# TSOC_ESP32S.net
KiCad netlist of a schematic drawn in EAGLE
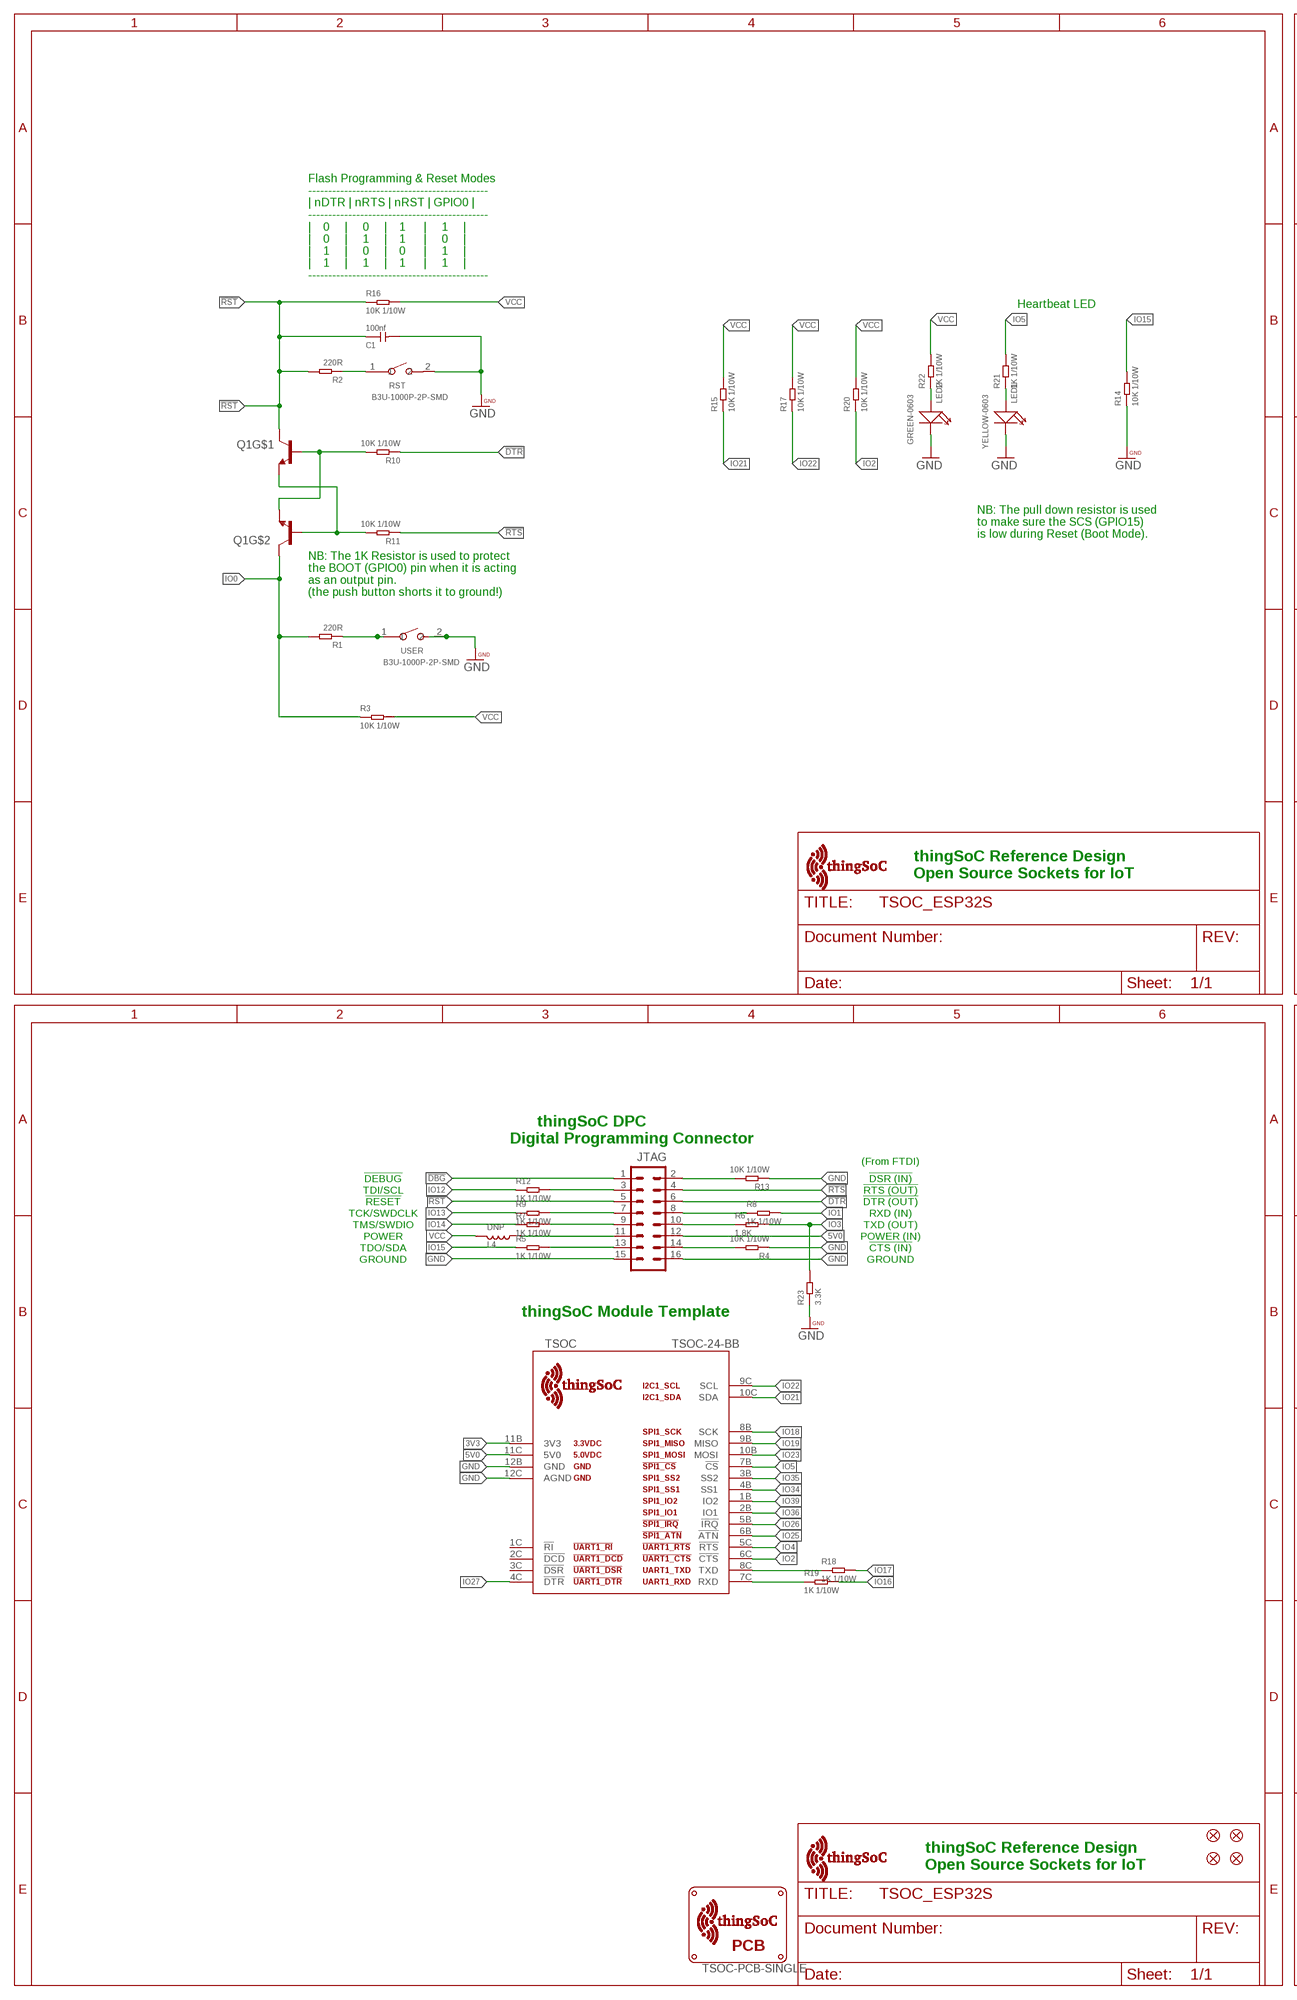
[diagram p0: schematic, sheet 1, part 1 of 2]
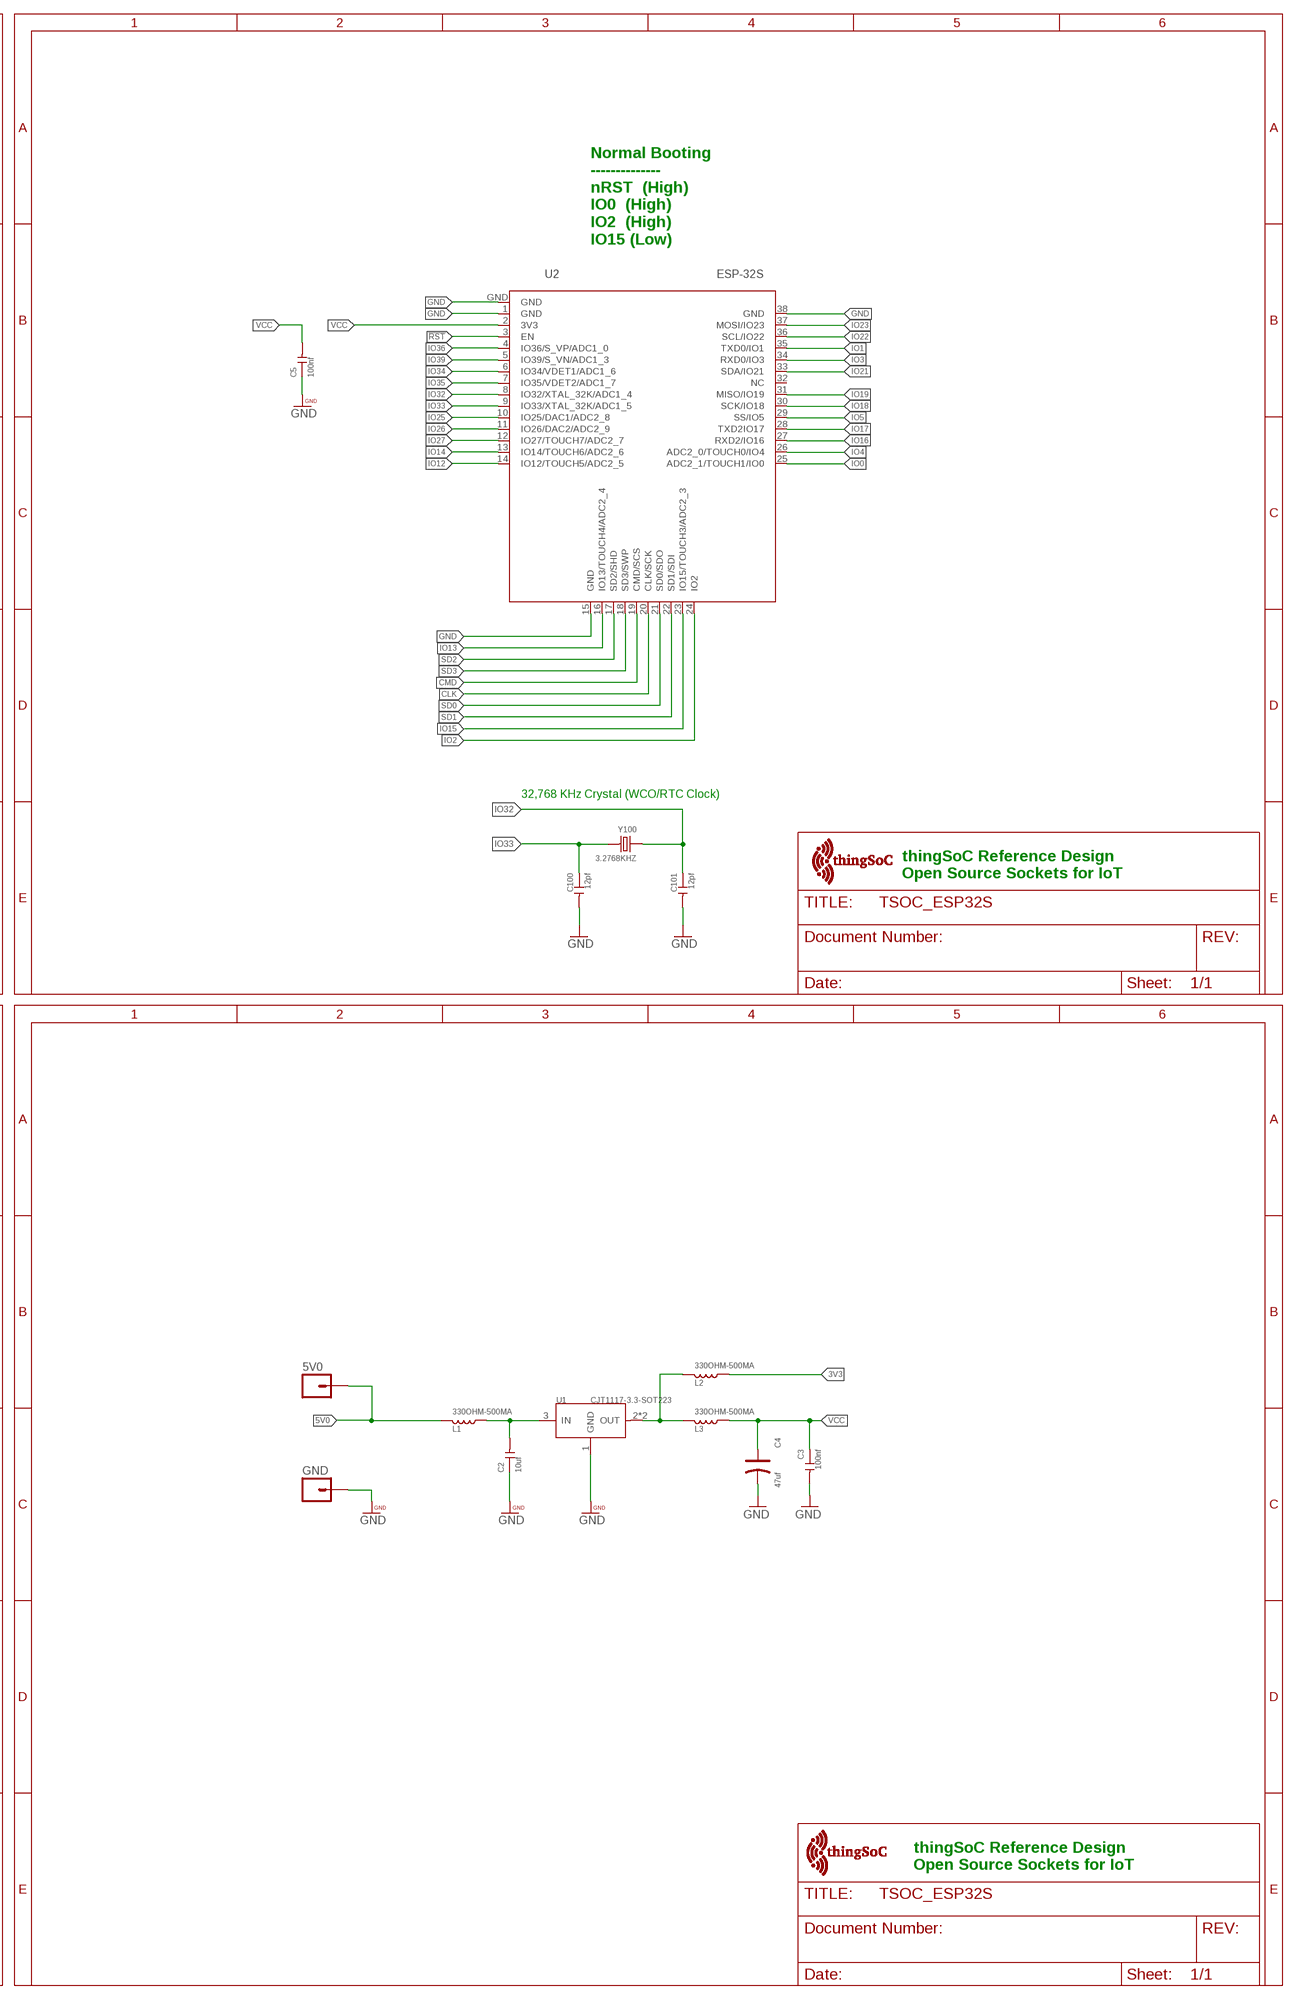
[diagram p1: schematic, sheet 1, part 2 of 2]

(export (version "E")
  (design (tool "Eeschema 10.0.6"))
  (components
    (comp (ref "$$U$1")
      (value "TSOC-LOGO-SMALL")
      (footprint "eagle-import:TSOC-LOGO-SML")
      (libsource (lib "eagle-import") (part "TSOC-LOGO-SMALL"))
    )
    (comp (ref "$$U$2")
      (value "TSOC-LOGO-SMALL")
      (footprint "eagle-import:TSOC-LOGO-SML")
      (libsource (lib "eagle-import") (part "TSOC-LOGO-SMALL"))
    )
    (comp (ref "5V0")
      (value "M01PTH")
      (footprint "eagle-import:1X01")
      (libsource (lib "eagle-import") (part "M01PTH"))
    )
    (comp (ref "BRD")
      (value "TSOC-PCB-SINGLE")
      (footprint "eagle-import:TSOC-BB-BRD-DIM")
      (libsource (lib "eagle-import") (part "TSOC-PCB-SINGLE"))
    )
    (comp (ref "C1")
      (value "100nf")
      (footprint "eagle-import:C0603")
      (fields (field (name "MPN") "CC0603KRX7R9BB104"))
      (libsource (lib "eagle-import") (part "CERAMIC-100NF-50V-10%-X7R(0603)"))
    )
    (comp (ref "C2")
      (value "10uf")
      (footprint "eagle-import:C0603")
      (fields (field (name "MPN") "CC0603KRX5R6BB106"))
      (libsource (lib "eagle-import") (part "CERAMIC-10UF-10V-10%-X5R(0603)"))
    )
    (comp (ref "C3")
      (value "100nf")
      (footprint "eagle-import:C0603")
      (fields (field (name "MPN") "CC0603KRX7R9BB104"))
      (libsource (lib "eagle-import") (part "CERAMIC-100NF-50V-10%-X7R(0603)"))
    )
    (comp (ref "C4")
      (value "47uf")
      (footprint "eagle-import:AVX-A")
      (fields (field (name "MPN") "TAJA476*006#NJ"))
      (libsource (lib "eagle-import") (part "TANTALUM-SMD-47UF-6.3V(AVX-A)"))
    )
    (comp (ref "C5")
      (value "100nf")
      (footprint "eagle-import:C0603")
      (fields (field (name "MPN") "CC0603KRX5R6BB106"))
      (libsource (lib "eagle-import") (part "CERAMIC-10UF-10V-10%-X5R(0603)"))
    )
    (comp (ref "C100")
      (value "12pf")
      (footprint "eagle-import:C0603")
      (fields (field (name "MPN") "CC0603JRNPO9BN120"))
      (libsource (lib "eagle-import") (part "CERAMIC-12PF-50V-5%-NPO(0603)"))
    )
    (comp (ref "C101")
      (value "12pf")
      (footprint "eagle-import:C0603")
      (fields (field (name "MPN") "CC0603JRNPO9BN120"))
      (libsource (lib "eagle-import") (part "CERAMIC-12PF-50V-5%-NPO(0603)"))
    )
    (comp (ref "FID1")
      (value "FIDUCIALUFIDUCIAL")
      (footprint "eagle-import:MICRO-FIDUCIAL")
      (libsource (lib "eagle-import") (part "FIDUCIALUFIDUCIAL"))
    )
    (comp (ref "FID2")
      (value "FIDUCIALUFIDUCIAL")
      (footprint "eagle-import:MICRO-FIDUCIAL")
      (libsource (lib "eagle-import") (part "FIDUCIALUFIDUCIAL"))
    )
    (comp (ref "FID3")
      (value "FIDUCIALUFIDUCIAL")
      (footprint "eagle-import:MICRO-FIDUCIAL")
      (libsource (lib "eagle-import") (part "FIDUCIALUFIDUCIAL"))
    )
    (comp (ref "FID4")
      (value "FIDUCIALUFIDUCIAL")
      (footprint "eagle-import:MICRO-FIDUCIAL")
      (libsource (lib "eagle-import") (part "FIDUCIALUFIDUCIAL"))
    )
    (comp (ref "GND")
      (value "M01PTH")
      (footprint "eagle-import:1X01")
      (libsource (lib "eagle-import") (part "M01PTH"))
    )
    (comp (ref "JTAG")
      (value "M08X2")
      (footprint "eagle-import:2X8")
      (libsource (lib "eagle-import") (part "M08X2"))
    )
    (comp (ref "L1")
      (value "330OHM-500MA")
      (footprint "eagle-import:L0603")
      (fields (field (name "MPN") "BLM18AG121SN1D"))
      (libsource (lib "eagle-import") (part "SMD-FERRITE-CHIP-120-OHM-500MA(0603)"))
    )
    (comp (ref "L2")
      (value "330OHM-500MA")
      (footprint "eagle-import:L0603")
      (fields (field (name "MPN") "BLM18AG121SN1D"))
      (libsource (lib "eagle-import") (part "SMD-FERRITE-CHIP-120-OHM-500MA(0603)"))
    )
    (comp (ref "L3")
      (value "330OHM-500MA")
      (footprint "eagle-import:L0603")
      (fields (field (name "MPN") "BLM18AG121SN1D"))
      (libsource (lib "eagle-import") (part "SMD-FERRITE-CHIP-120-OHM-500MA(0603)"))
    )
    (comp (ref "L4")
      (value "DNP")
      (footprint "eagle-import:L0603")
      (fields (field (name "MPN") "BLM18AG121SN1D"))
      (libsource (lib "eagle-import") (part "SMD-FERRITE-CHIP-120-OHM-500MA(0603)"))
    )
    (comp (ref "LED1")
      (value "YELLOW-0603")
      (footprint "eagle-import:LED-0603")
      (fields (field (name "MPN") "19-217-Y5C-AM1N1VY-3T"))
      (libsource (lib "eagle-import") (part "SMD-LED-CLEAR-YELLOW(0603)"))
    )
    (comp (ref "LED2")
      (value "GREEN-0603")
      (footprint "eagle-import:LED-0603")
      (fields (field (name "MPN") "19-217-G7C-AN1P2-3T"))
      (libsource (lib "eagle-import") (part "SMD-LED-CLEAR-GREEN(0603)"))
    )
    (comp (ref "Q1")
      (value "MMBT2222A")
      (footprint "eagle-import:SOT363")
      (libsource (lib "eagle-import") (part "MMDT3904"))
    )
    (comp (ref "R1")
      (value "220R")
      (footprint "eagle-import:R0603")
      (fields (field (name "MPN") "RC0603JR-07220RL"))
      (libsource (lib "eagle-import") (part "SMD-RES-220R-5%-1/10W(0603)"))
    )
    (comp (ref "R2")
      (value "220R")
      (footprint "eagle-import:R0603")
      (fields (field (name "MPN") "RC0603JR-07220RL"))
      (libsource (lib "eagle-import") (part "SMD-RES-220R-5%-1/10W(0603)"))
    )
    (comp (ref "R3")
      (value "10K 1/10W")
      (footprint "eagle-import:R0603")
      (fields (field (name "MPN") "RC0603JR-0710KL"))
      (libsource (lib "eagle-import") (part "SMD-RES-10K-5%-1/10W(0603)"))
    )
    (comp (ref "R4")
      (value "10K 1/10W")
      (footprint "eagle-import:R0603")
      (fields (field (name "MPN") "RC0603JR-0710KL"))
      (libsource (lib "eagle-import") (part "SMD-RES-10K-5%-1/10W(0603)"))
    )
    (comp (ref "R5")
      (value "1K 1/10W")
      (footprint "eagle-import:R0603")
      (fields (field (name "MPN") "RC0603JR-071KL"))
      (libsource (lib "eagle-import") (part "SMD-RES-1K-5%-1/10W(0603)"))
    )
    (comp (ref "R6")
      (value "1.8K")
      (footprint "eagle-import:R0603")
      (fields (field (name "MPN") "RC0603FR-071K8L"))
      (libsource (lib "eagle-import") (part "SMD-RES-1.8K-1%-1/10W(0603)"))
    )
    (comp (ref "R7")
      (value "1K 1/10W")
      (footprint "eagle-import:R0603")
      (fields (field (name "MPN") "RC0603JR-071KL"))
      (libsource (lib "eagle-import") (part "SMD-RES-1K-5%-1/10W(0603)"))
    )
    (comp (ref "R8")
      (value "1K 1/10W")
      (footprint "eagle-import:R0603")
      (fields (field (name "MPN") "RC0603JR-071KL"))
      (libsource (lib "eagle-import") (part "SMD-RES-1K-5%-1/10W(0603)"))
    )
    (comp (ref "R9")
      (value "1K 1/10W")
      (footprint "eagle-import:R0603")
      (fields (field (name "MPN") "RC0603JR-071KL"))
      (libsource (lib "eagle-import") (part "SMD-RES-1K-5%-1/10W(0603)"))
    )
    (comp (ref "R10")
      (value "10K 1/10W")
      (footprint "eagle-import:R0603")
      (fields (field (name "MPN") "RC0603JR-0710KL"))
      (libsource (lib "eagle-import") (part "SMD-RES-10K-5%-1/10W(0603)"))
    )
    (comp (ref "R11")
      (value "10K 1/10W")
      (footprint "eagle-import:R0603")
      (fields (field (name "MPN") "RC0603JR-0710KL"))
      (libsource (lib "eagle-import") (part "SMD-RES-10K-5%-1/10W(0603)"))
    )
    (comp (ref "R12")
      (value "1K 1/10W")
      (footprint "eagle-import:R0603")
      (fields (field (name "MPN") "RC0603JR-071KL"))
      (libsource (lib "eagle-import") (part "SMD-RES-1K-5%-1/10W(0603)"))
    )
    (comp (ref "R13")
      (value "10K 1/10W")
      (footprint "eagle-import:R0603")
      (fields (field (name "MPN") "RC0603JR-0710KL"))
      (libsource (lib "eagle-import") (part "SMD-RES-10K-5%-1/10W(0603)"))
    )
    (comp (ref "R14")
      (value "10K 1/10W")
      (footprint "eagle-import:R0603")
      (fields (field (name "MPN") "RC0603JR-0710KL"))
      (libsource (lib "eagle-import") (part "SMD-RES-10K-5%-1/10W(0603)"))
    )
    (comp (ref "R15")
      (value "10K 1/10W")
      (footprint "eagle-import:R0603")
      (fields (field (name "MPN") "RC0603JR-0710KL"))
      (libsource (lib "eagle-import") (part "SMD-RES-10K-5%-1/10W(0603)"))
    )
    (comp (ref "R16")
      (value "10K 1/10W")
      (footprint "eagle-import:R0603")
      (fields (field (name "MPN") "RC0603JR-0710KL"))
      (libsource (lib "eagle-import") (part "SMD-RES-10K-5%-1/10W(0603)"))
    )
    (comp (ref "R17")
      (value "10K 1/10W")
      (footprint "eagle-import:R0603")
      (fields (field (name "MPN") "RC0603JR-0710KL"))
      (libsource (lib "eagle-import") (part "SMD-RES-10K-5%-1/10W(0603)"))
    )
    (comp (ref "R18")
      (value "1K 1/10W")
      (footprint "eagle-import:R0603")
      (fields (field (name "MPN") "RC0603JR-071KL"))
      (libsource (lib "eagle-import") (part "SMD-RES-1K-5%-1/10W(0603)"))
    )
    (comp (ref "R19")
      (value "1K 1/10W")
      (footprint "eagle-import:R0603")
      (fields (field (name "MPN") "RC0603JR-071KL"))
      (libsource (lib "eagle-import") (part "SMD-RES-1K-5%-1/10W(0603)"))
    )
    (comp (ref "R20")
      (value "10K 1/10W")
      (footprint "eagle-import:R0603")
      (fields (field (name "MPN") "RC0603JR-0710KL"))
      (libsource (lib "eagle-import") (part "SMD-RES-10K-5%-1/10W(0603)"))
    )
    (comp (ref "R21")
      (value "1K 1/10W")
      (footprint "eagle-import:R0603")
      (fields (field (name "MPN") "RC0603JR-071KL"))
      (libsource (lib "eagle-import") (part "SMD-RES-1K-5%-1/10W(0603)"))
    )
    (comp (ref "R22")
      (value "1K 1/10W")
      (footprint "eagle-import:R0603")
      (fields (field (name "MPN") "RC0603JR-071KL"))
      (libsource (lib "eagle-import") (part "SMD-RES-1K-5%-1/10W(0603)"))
    )
    (comp (ref "R23")
      (value "3.3K")
      (footprint "eagle-import:R0603")
      (fields (field (name "MPN") "RC0603FR-073K3L"))
      (libsource (lib "eagle-import") (part "SMD-RES-3.3K-1%-1/10W(0603)"))
    )
    (comp (ref "RST")
      (value "B3U-1000P-2P-SMD")
      (footprint "eagle-import:SW2-2.6-3.0X2.5X1.2+0.4MM")
      (libsource (lib "eagle-import") (part "SMD-BUTTON(2P-3.0X2.5X1.2+0.4MM)-B3U-1000P-2P-SMD"))
    )
    (comp (ref "TSOC")
      (value "TSOC-24-BB")
      (footprint "eagle-import:TSOC-BB-S24")
      (libsource (lib "eagle-import") (part "TSOC-24-BB"))
    )
    (comp (ref "U$101")
      (value "TSOC-LOGO-SMALL")
      (footprint "eagle-import:TSOC-LOGO-SML")
      (libsource (lib "eagle-import") (part "TSOC-LOGO-SMALL"))
    )
    (comp (ref "U$102")
      (value "TSOC-LOGO-LRG")
      (footprint "eagle-import:TSOC-LOGO-LRG")
      (libsource (lib "eagle-import") (part "TSOC-LOGO-LRG"))
    )
    (comp (ref "U1")
      (value "CJT1117-3.3-SOT223")
      (footprint "eagle-import:SOT-223")
      (fields (field (name "MPN") "CJT1117-3.3"))
      (libsource (lib "eagle-import") (part "PMIC-CJT1117-3.3(SOT223)"))
    )
    (comp (ref "U2")
      (value "ESP-32S")
      (footprint "eagle-import:ESP-32S")
      (libsource (lib "eagle-import") (part "ESP-32S"))
    )
    (comp (ref "USER")
      (value "B3U-1000P-2P-SMD")
      (footprint "eagle-import:SW2-2.6-3.0X2.5X1.2+0.4MM")
      (libsource (lib "eagle-import") (part "SMD-BUTTON(2P-3.0X2.5X1.2+0.4MM)-B3U-1000P-2P-SMD"))
    )
    (comp (ref "Y100")
      (value "3.2768KHZ")
      (footprint "eagle-import:X2-SMD-L2.0X1.2X0.55MM")
      (fields (field (name "MPN") "FC-12M"))
      (libsource (lib "eagle-import") (part "SMD-CRYSTAL-32.768KHZ-12.5PF-20PPM-90K(2P-L2.0X1.2MM)"))
    )
  )
  (nets
    (net (code "1") (name "/~{DBG}") (class "Default")
      (node (ref "JTAG") (pin "1") (pinfunction "1_1") (pintype "passive"))
    )
    (net (code "2") (name "/~{DTR}") (class "Default")
      (node (ref "JTAG") (pin "6") (pinfunction "6_6") (pintype "passive"))
      (node (ref "R10") (pin "1") (pinfunction "1_1") (pintype "passive"))
    )
    (net (code "3") (name "/~{RST}") (class "Default")
      (node (ref "C1") (pin "1") (pinfunction "1_1") (pintype "passive"))
      (node (ref "JTAG") (pin "5") (pinfunction "5_5") (pintype "passive"))
      (node (ref "Q1") (pin "3") (pinfunction "C_3") (pintype "passive"))
      (node (ref "R16") (pin "1") (pinfunction "1_1") (pintype "passive"))
      (node (ref "R2") (pin "2") (pinfunction "2_2") (pintype "passive"))
      (node (ref "U2") (pin "3") (pinfunction "EN_3") (pintype "bidirectional"))
    )
    (net (code "4") (name "/~{RTS}") (class "Default")
      (node (ref "JTAG") (pin "4") (pinfunction "4_4") (pintype "passive"))
      (node (ref "R11") (pin "1") (pinfunction "1_1") (pintype "passive"))
    )
    (net (code "5") (name "3V3") (class "Default")
      (node (ref "L2") (pin "2") (pinfunction "2_2") (pintype "passive"))
      (node (ref "TSOC") (pin "11B") (pinfunction "3V3_11B") (pintype "bidirectional"))
    )
    (net (code "6") (name "5V0") (class "Default")
      (node (ref "5V0") (pin "1") (pinfunction "1_1") (pintype "passive"))
      (node (ref "JTAG") (pin "12") (pinfunction "12_12") (pintype "passive"))
      (node (ref "L1") (pin "1") (pinfunction "1_1") (pintype "passive"))
      (node (ref "TSOC") (pin "11C") (pinfunction "5V0_11C") (pintype "bidirectional"))
    )
    (net (code "7") (name "CLK") (class "Default")
      (node (ref "U2") (pin "20") (pinfunction "CLK/SCK_20") (pintype "bidirectional"))
    )
    (net (code "8") (name "CMD") (class "Default")
      (node (ref "U2") (pin "19") (pinfunction "CMD/SCS_19") (pintype "bidirectional"))
    )
    (net (code "9") (name "GND") (class "Default")
      (node (ref "C1") (pin "2") (pinfunction "2_2") (pintype "passive"))
      (node (ref "C100") (pin "2") (pinfunction "2_2") (pintype "passive"))
      (node (ref "C101") (pin "2") (pinfunction "2_2") (pintype "passive"))
      (node (ref "C2") (pin "1") (pinfunction "1_1") (pintype "passive"))
      (node (ref "C3") (pin "2") (pinfunction "2_2") (pintype "passive"))
      (node (ref "C4") (pin "-") (pinfunction "-_-") (pintype "passive"))
      (node (ref "C5") (pin "1") (pinfunction "1_1") (pintype "passive"))
      (node (ref "GND") (pin "1") (pinfunction "1_1") (pintype "passive"))
      (node (ref "JTAG") (pin "15") (pinfunction "15_15") (pintype "passive"))
      (node (ref "JTAG") (pin "16") (pinfunction "16_16") (pintype "passive"))
      (node (ref "LED1") (pin "-") (pinfunction "-_-") (pintype "passive"))
      (node (ref "LED2") (pin "-") (pinfunction "-_-") (pintype "passive"))
      (node (ref "R13") (pin "1") (pinfunction "1_1") (pintype "passive"))
      (node (ref "R14") (pin "1") (pinfunction "1_1") (pintype "passive"))
      (node (ref "R23") (pin "1") (pinfunction "1_1") (pintype "passive"))
      (node (ref "R4") (pin "1") (pinfunction "1_1") (pintype "passive"))
      (node (ref "RST") (pin "2") (pinfunction "2_2") (pintype "bidirectional"))
      (node (ref "TSOC") (pin "12B") (pinfunction "GND_12B") (pintype "bidirectional"))
      (node (ref "TSOC") (pin "12C") (pinfunction "AGND_12C") (pintype "bidirectional"))
      (node (ref "U1") (pin "1") (pinfunction "GND_1") (pintype "bidirectional"))
      (node (ref "U2") (pin "1") (pinfunction "GND_1") (pintype "bidirectional"))
      (node (ref "U2") (pin "15") (pinfunction "GND_15") (pintype "bidirectional"))
      (node (ref "U2") (pin "38") (pinfunction "GND_38") (pintype "bidirectional"))
      (node (ref "U2") (pin "GND") (pinfunction "GND_GND") (pintype "bidirectional"))
      (node (ref "USER") (pin "2") (pinfunction "2_2") (pintype "bidirectional"))
    )
    (net (code "10") (name "IO0") (class "Default")
      (node (ref "Q1") (pin "6") (pinfunction "C_6") (pintype "passive"))
      (node (ref "R1") (pin "2") (pinfunction "2_2") (pintype "passive"))
      (node (ref "R3") (pin "1") (pinfunction "1_1") (pintype "passive"))
      (node (ref "U2") (pin "25") (pinfunction "ADC2_1/TOUCH1/IO0_25") (pintype "bidirectional"))
    )
    (net (code "11") (name "IO1") (class "Default")
      (node (ref "R8") (pin "2") (pinfunction "2_2") (pintype "passive"))
      (node (ref "U2") (pin "35") (pinfunction "TXD0/IO1_35") (pintype "bidirectional"))
    )
    (net (code "12") (name "IO2") (class "Default")
      (node (ref "R20") (pin "1") (pinfunction "1_1") (pintype "passive"))
      (node (ref "TSOC") (pin "6C") (pinfunction "~{CTS}_6C") (pintype "bidirectional"))
      (node (ref "U2") (pin "24") (pinfunction "IO2_24") (pintype "bidirectional"))
    )
    (net (code "13") (name "IO3") (class "Default")
      (node (ref "R23") (pin "2") (pinfunction "2_2") (pintype "passive"))
      (node (ref "R6") (pin "2") (pinfunction "2_2") (pintype "passive"))
      (node (ref "U2") (pin "34") (pinfunction "RXD0/IO3_34") (pintype "bidirectional"))
    )
    (net (code "14") (name "IO4") (class "Default")
      (node (ref "TSOC") (pin "5C") (pinfunction "~{RTS}_5C") (pintype "bidirectional"))
      (node (ref "U2") (pin "26") (pinfunction "ADC2_0/TOUCH0/IO4_26") (pintype "bidirectional"))
    )
    (net (code "15") (name "IO5") (class "Default")
      (node (ref "R21") (pin "2") (pinfunction "2_2") (pintype "passive"))
      (node (ref "TSOC") (pin "7B") (pinfunction "~{CS}_7B") (pintype "bidirectional"))
      (node (ref "U2") (pin "29") (pinfunction "SS/IO5_29") (pintype "bidirectional"))
    )
    (net (code "16") (name "IO12") (class "Default")
      (node (ref "R12") (pin "1") (pinfunction "1_1") (pintype "passive"))
      (node (ref "U2") (pin "14") (pinfunction "IO12/TOUCH5/ADC2_5_14") (pintype "bidirectional"))
    )
    (net (code "17") (name "IO13") (class "Default")
      (node (ref "R9") (pin "1") (pinfunction "1_1") (pintype "passive"))
      (node (ref "U2") (pin "16") (pinfunction "IO13/TOUCH4/ADC2_4_16") (pintype "bidirectional"))
    )
    (net (code "18") (name "IO14") (class "Default")
      (node (ref "R7") (pin "1") (pinfunction "1_1") (pintype "passive"))
      (node (ref "U2") (pin "13") (pinfunction "IO14/TOUCH6/ADC2_6_13") (pintype "bidirectional"))
    )
    (net (code "19") (name "IO15") (class "Default")
      (node (ref "R14") (pin "2") (pinfunction "2_2") (pintype "passive"))
      (node (ref "R5") (pin "1") (pinfunction "1_1") (pintype "passive"))
      (node (ref "U2") (pin "23") (pinfunction "IO15/TOUCH3/ADC2_3_23") (pintype "bidirectional"))
    )
    (net (code "20") (name "IO16") (class "Default")
      (node (ref "R19") (pin "2") (pinfunction "2_2") (pintype "passive"))
      (node (ref "U2") (pin "27") (pinfunction "RXD2/IO16_27") (pintype "bidirectional"))
    )
    (net (code "21") (name "IO17") (class "Default")
      (node (ref "R18") (pin "2") (pinfunction "2_2") (pintype "passive"))
      (node (ref "U2") (pin "28") (pinfunction "TXD2IO17_28") (pintype "bidirectional"))
    )
    (net (code "22") (name "IO18") (class "Default")
      (node (ref "TSOC") (pin "8B") (pinfunction "SCK_8B") (pintype "bidirectional"))
      (node (ref "U2") (pin "30") (pinfunction "SCK/IO18_30") (pintype "bidirectional"))
    )
    (net (code "23") (name "IO19") (class "Default")
      (node (ref "TSOC") (pin "9B") (pinfunction "MISO_9B") (pintype "bidirectional"))
      (node (ref "U2") (pin "31") (pinfunction "MISO/IO19_31") (pintype "bidirectional"))
    )
    (net (code "24") (name "IO21") (class "Default")
      (node (ref "R15") (pin "1") (pinfunction "1_1") (pintype "passive"))
      (node (ref "TSOC") (pin "10C") (pinfunction "SDA_10C") (pintype "bidirectional"))
      (node (ref "U2") (pin "33") (pinfunction "SDA/IO21_33") (pintype "bidirectional"))
    )
    (net (code "25") (name "IO22") (class "Default")
      (node (ref "R17") (pin "1") (pinfunction "1_1") (pintype "passive"))
      (node (ref "TSOC") (pin "9C") (pinfunction "SCL_9C") (pintype "bidirectional"))
      (node (ref "U2") (pin "36") (pinfunction "SCL/IO22_36") (pintype "bidirectional"))
    )
    (net (code "26") (name "IO23") (class "Default")
      (node (ref "TSOC") (pin "10B") (pinfunction "MOSI_10B") (pintype "bidirectional"))
      (node (ref "U2") (pin "37") (pinfunction "MOSI/IO23_37") (pintype "bidirectional"))
    )
    (net (code "27") (name "IO25") (class "Default")
      (node (ref "TSOC") (pin "6B") (pinfunction "~{ATN}_6B") (pintype "bidirectional"))
      (node (ref "U2") (pin "10") (pinfunction "IO25/DAC1/ADC2_8_10") (pintype "bidirectional"))
    )
    (net (code "28") (name "IO26") (class "Default")
      (node (ref "TSOC") (pin "5B") (pinfunction "~{IRQ}_5B") (pintype "bidirectional"))
      (node (ref "U2") (pin "11") (pinfunction "IO26/DAC2/ADC2_9_11") (pintype "bidirectional"))
    )
    (net (code "29") (name "IO27") (class "Default")
      (node (ref "TSOC") (pin "4C") (pinfunction "~{DTR}_4C") (pintype "bidirectional"))
      (node (ref "U2") (pin "12") (pinfunction "IO27/TOUCH7/ADC2_7_12") (pintype "bidirectional"))
    )
    (net (code "30") (name "IO32") (class "Default")
      (node (ref "C101") (pin "1") (pinfunction "1_1") (pintype "passive"))
      (node (ref "U2") (pin "8") (pinfunction "IO32/XTAL_32K/ADC1_4_8") (pintype "bidirectional"))
      (node (ref "Y100") (pin "1") (pinfunction "1_1") (pintype "passive"))
    )
    (net (code "31") (name "IO33") (class "Default")
      (node (ref "C100") (pin "1") (pinfunction "1_1") (pintype "passive"))
      (node (ref "U2") (pin "9") (pinfunction "IO33/XTAL_32K/ADC1_5_9") (pintype "bidirectional"))
      (node (ref "Y100") (pin "2") (pinfunction "2_2") (pintype "passive"))
    )
    (net (code "32") (name "IO34") (class "Default")
      (node (ref "TSOC") (pin "4B") (pinfunction "SS1_4B") (pintype "bidirectional"))
      (node (ref "U2") (pin "6") (pinfunction "IO34/VDET1/ADC1_6_6") (pintype "bidirectional"))
    )
    (net (code "33") (name "IO35") (class "Default")
      (node (ref "TSOC") (pin "3B") (pinfunction "SS2_3B") (pintype "bidirectional"))
      (node (ref "U2") (pin "7") (pinfunction "IO35/VDET2/ADC1_7_7") (pintype "bidirectional"))
    )
    (net (code "34") (name "IO36") (class "Default")
      (node (ref "TSOC") (pin "2B") (pinfunction "IO1_2B") (pintype "bidirectional"))
      (node (ref "U2") (pin "4") (pinfunction "IO36/S_VP/ADC1_0_4") (pintype "bidirectional"))
    )
    (net (code "35") (name "IO39") (class "Default")
      (node (ref "TSOC") (pin "1B") (pinfunction "IO2_1B") (pintype "bidirectional"))
      (node (ref "U2") (pin "5") (pinfunction "IO39/S_VN/ADC1_3_5") (pintype "bidirectional"))
    )
    (net (code "36") (name "Net-(JTAG-Pad2)") (class "Default")
      (node (ref "JTAG") (pin "2") (pinfunction "2_2") (pintype "passive"))
      (node (ref "R13") (pin "2") (pinfunction "2_2") (pintype "passive"))
    )
    (net (code "37") (name "Net-(JTAG-Pad3)") (class "Default")
      (node (ref "JTAG") (pin "3") (pinfunction "3_3") (pintype "passive"))
      (node (ref "R12") (pin "2") (pinfunction "2_2") (pintype "passive"))
    )
    (net (code "38") (name "Net-(JTAG-Pad7)") (class "Default")
      (node (ref "JTAG") (pin "7") (pinfunction "7_7") (pintype "passive"))
      (node (ref "R9") (pin "2") (pinfunction "2_2") (pintype "passive"))
    )
    (net (code "39") (name "Net-(JTAG-Pad8)") (class "Default")
      (node (ref "JTAG") (pin "8") (pinfunction "8_8") (pintype "passive"))
      (node (ref "R8") (pin "1") (pinfunction "1_1") (pintype "passive"))
    )
    (net (code "40") (name "Net-(JTAG-Pad9)") (class "Default")
      (node (ref "JTAG") (pin "9") (pinfunction "9_9") (pintype "passive"))
      (node (ref "R7") (pin "2") (pinfunction "2_2") (pintype "passive"))
    )
    (net (code "41") (name "Net-(JTAG-Pad10)") (class "Default")
      (node (ref "JTAG") (pin "10") (pinfunction "10_10") (pintype "passive"))
      (node (ref "R6") (pin "1") (pinfunction "1_1") (pintype "passive"))
    )
    (net (code "42") (name "Net-(JTAG-Pad11)") (class "Default")
      (node (ref "JTAG") (pin "11") (pinfunction "11_11") (pintype "passive"))
      (node (ref "L4") (pin "2") (pinfunction "2_2") (pintype "passive"))
    )
    (net (code "43") (name "Net-(JTAG-Pad13)") (class "Default")
      (node (ref "JTAG") (pin "13") (pinfunction "13_13") (pintype "passive"))
      (node (ref "R5") (pin "2") (pinfunction "2_2") (pintype "passive"))
    )
    (net (code "44") (name "Net-(JTAG-Pad14)") (class "Default")
      (node (ref "JTAG") (pin "14") (pinfunction "14_14") (pintype "passive"))
      (node (ref "R4") (pin "2") (pinfunction "2_2") (pintype "passive"))
    )
    (net (code "45") (name "Net-(L2-Pad1)") (class "Default")
      (node (ref "L2") (pin "1") (pinfunction "1_1") (pintype "passive"))
      (node (ref "L3") (pin "1") (pinfunction "1_1") (pintype "passive"))
      (node (ref "U1") (pin "2") (pinfunction "OUT_2") (pintype "bidirectional"))
      (node (ref "U1") (pin "TER") (pinfunction "OUT_TER") (pintype "bidirectional"))
    )
    (net (code "46") (name "Net-(LED1-Pad+)") (class "Default")
      (node (ref "LED1") (pin "+") (pinfunction "+_+") (pintype "passive"))
      (node (ref "R21") (pin "1") (pinfunction "1_1") (pintype "passive"))
    )
    (net (code "47") (name "Net-(LED2-Pad+)") (class "Default")
      (node (ref "LED2") (pin "+") (pinfunction "+_+") (pintype "passive"))
      (node (ref "R22") (pin "1") (pinfunction "1_1") (pintype "passive"))
    )
    (net (code "48") (name "Net-(Q1A-B)") (class "Default")
      (node (ref "Q1") (pin "1") (pinfunction "E_1") (pintype "passive"))
      (node (ref "Q1") (pin "5") (pinfunction "B_5") (pintype "passive"))
      (node (ref "R10") (pin "2") (pinfunction "2_2") (pintype "passive"))
    )
    (net (code "49") (name "Net-(Q1A-E)") (class "Default")
      (node (ref "Q1") (pin "2") (pinfunction "B_2") (pintype "passive"))
      (node (ref "Q1") (pin "4") (pinfunction "E_4") (pintype "passive"))
      (node (ref "R11") (pin "2") (pinfunction "2_2") (pintype "passive"))
    )
    (net (code "50") (name "Net-(R1-Pad1)") (class "Default")
      (node (ref "R1") (pin "1") (pinfunction "1_1") (pintype "passive"))
      (node (ref "USER") (pin "1") (pinfunction "1_1") (pintype "bidirectional"))
    )
    (net (code "51") (name "Net-(R2-Pad1)") (class "Default")
      (node (ref "R2") (pin "1") (pinfunction "1_1") (pintype "passive"))
      (node (ref "RST") (pin "1") (pinfunction "1_1") (pintype "bidirectional"))
    )
    (net (code "52") (name "Net-(TSOC-RXD)") (class "Default")
      (node (ref "R19") (pin "1") (pinfunction "1_1") (pintype "passive"))
      (node (ref "TSOC") (pin "7C") (pinfunction "RXD_7C") (pintype "bidirectional"))
    )
    (net (code "53") (name "Net-(TSOC-TXD)") (class "Default")
      (node (ref "R18") (pin "1") (pinfunction "1_1") (pintype "passive"))
      (node (ref "TSOC") (pin "8C") (pinfunction "TXD_8C") (pintype "bidirectional"))
    )
    (net (code "54") (name "Net-(U1-IN)") (class "Default")
      (node (ref "C2") (pin "2") (pinfunction "2_2") (pintype "passive"))
      (node (ref "L1") (pin "2") (pinfunction "2_2") (pintype "passive"))
      (node (ref "U1") (pin "3") (pinfunction "IN_3") (pintype "bidirectional"))
    )
    (net (code "55") (name "SD0") (class "Default")
      (node (ref "U2") (pin "21") (pinfunction "SD0/SDO_21") (pintype "bidirectional"))
    )
    (net (code "56") (name "SD1") (class "Default")
      (node (ref "U2") (pin "22") (pinfunction "SD1/SDI_22") (pintype "bidirectional"))
    )
    (net (code "57") (name "SD2") (class "Default")
      (node (ref "U2") (pin "17") (pinfunction "SD2/SHD_17") (pintype "bidirectional"))
    )
    (net (code "58") (name "SD3") (class "Default")
      (node (ref "U2") (pin "18") (pinfunction "SD3/SWP_18") (pintype "bidirectional"))
    )
    (net (code "59") (name "VCC") (class "Default")
      (node (ref "C3") (pin "1") (pinfunction "1_1") (pintype "passive"))
      (node (ref "C4") (pin "+") (pinfunction "+_+") (pintype "passive"))
      (node (ref "C5") (pin "2") (pinfunction "2_2") (pintype "passive"))
      (node (ref "L3") (pin "2") (pinfunction "2_2") (pintype "passive"))
      (node (ref "L4") (pin "1") (pinfunction "1_1") (pintype "passive"))
      (node (ref "R15") (pin "2") (pinfunction "2_2") (pintype "passive"))
      (node (ref "R16") (pin "2") (pinfunction "2_2") (pintype "passive"))
      (node (ref "R17") (pin "2") (pinfunction "2_2") (pintype "passive"))
      (node (ref "R20") (pin "2") (pinfunction "2_2") (pintype "passive"))
      (node (ref "R22") (pin "2") (pinfunction "2_2") (pintype "passive"))
      (node (ref "R3") (pin "2") (pinfunction "2_2") (pintype "passive"))
      (node (ref "U2") (pin "2") (pinfunction "3V3_2") (pintype "bidirectional"))
    )
    (net (code "60") (name "unconnected-(TSOC-~{DCD}-Pad2C)") (class "Default")
      (node (ref "TSOC") (pin "2C") (pinfunction "~{DCD}_2C") (pintype "bidirectional"))
    )
    (net (code "61") (name "unconnected-(TSOC-~{DSR}-Pad3C)") (class "Default")
      (node (ref "TSOC") (pin "3C") (pinfunction "~{DSR}_3C") (pintype "bidirectional"))
    )
    (net (code "62") (name "unconnected-(TSOC-~{RI}-Pad1C)") (class "Default")
      (node (ref "TSOC") (pin "1C") (pinfunction "~{RI}_1C") (pintype "bidirectional"))
    )
    (net (code "63") (name "unconnected-(U2-NC-Pad32)") (class "Default")
      (node (ref "U2") (pin "32") (pinfunction "NC_32") (pintype "bidirectional"))
    )
  )
)
